# fuzz.net
KiCad netlist of a schematic drawn in Altium Designer
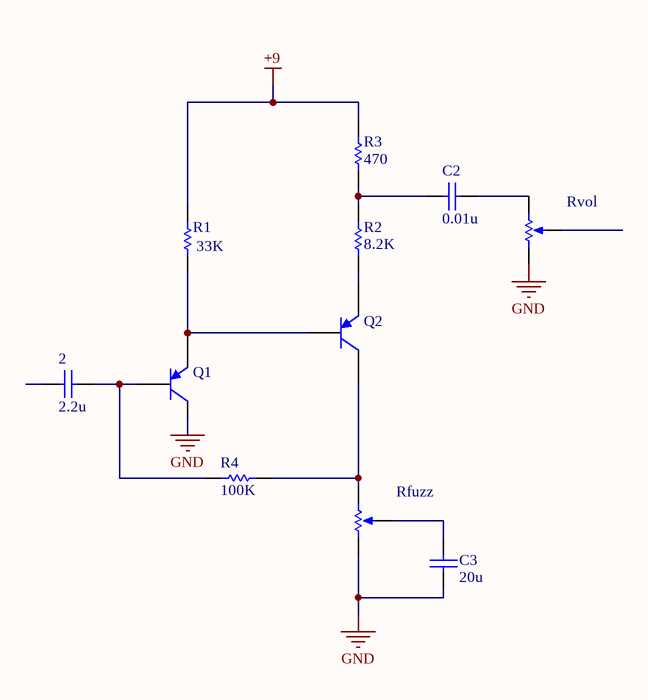
[diagram p0: fuzz.SchDoc]

(export (version "E")
  (design (tool "Eeschema 10.0.6"))
  (components
    (comp (ref "2")
      (value "2.2u")
      (description "Capacitor")
      (libsource (lib "Simulation Generic Components") (part "Capacitor"))
    )
    (comp (ref "C2")
      (value "0.01u")
      (description "Capacitor")
      (libsource (lib "Simulation Generic Components") (part "Capacitor"))
    )
    (comp (ref "C3")
      (value "20u")
      (description "Capacitor")
      (libsource (lib "Simulation Generic Components") (part "Capacitor"))
    )
    (comp (ref "Q1")
      (value "Bipolar PNP 3 Pins Transistor Gummel-Poon Model")
      (libsource (lib "Simulation Generic Components") (part "BJT PNP GP"))
    )
    (comp (ref "Q2")
      (value "Bipolar PNP 3 Pins Transistor Gummel-Poon Model")
      (libsource (lib "Simulation Generic Components") (part "BJT PNP GP"))
    )
    (comp (ref "R1")
      (value "33K")
      (description "Resistor")
      (libsource (lib "Simulation Generic Components") (part "Resistor"))
    )
    (comp (ref "R2")
      (value "8.2K")
      (description "Resistor")
      (libsource (lib "Simulation Generic Components") (part "Resistor"))
    )
    (comp (ref "R3")
      (value "470")
      (description "Resistor")
      (libsource (lib "Simulation Generic Components") (part "Resistor"))
    )
    (comp (ref "R4")
      (value "100K")
      (description "Resistor")
      (libsource (lib "Simulation Generic Components") (part "Resistor"))
    )
    (comp (ref "Rfuzz")
      (value "Potentiometer")
      (libsource (lib "Simulation Generic Components") (part "Potentiometer"))
    )
    (comp (ref "Rvol")
      (value "Potentiometer")
      (libsource (lib "Simulation Generic Components") (part "Potentiometer"))
    )
  )
  (nets
    (net (code "1") (name "+9") (class "Default")
      (node (ref "R1") (pin "1") (pinfunction "1_1") (pintype "passive"))
      (node (ref "R3") (pin "2") (pinfunction "2_2") (pintype "passive"))
    )
    (net (code "2") (name "GND") (class "Default")
      (node (ref "C3") (pin "1") (pinfunction "1_1") (pintype "passive"))
      (node (ref "Q1") (pin "1") (pinfunction "C_1") (pintype "passive"))
      (node (ref "Rfuzz") (pin "1") (pinfunction "TOP_1") (pintype "passive"))
      (node (ref "Rvol") (pin "1") (pinfunction "TOP_1") (pintype "passive"))
    )
    (net (code "3") (name "Net-(C2-Pad1)") (class "Default")
      (node (ref "C2") (pin "1") (pinfunction "1_1") (pintype "passive"))
      (node (ref "R2") (pin "2") (pinfunction "2_2") (pintype "passive"))
      (node (ref "R3") (pin "1") (pinfunction "1_1") (pintype "passive"))
    )
    (net (code "4") (name "Net-(Q1-B)") (class "Default")
      (node (ref "2") (pin "2") (pinfunction "2_2") (pintype "passive"))
      (node (ref "Q1") (pin "2") (pinfunction "B_2") (pintype "passive"))
      (node (ref "R4") (pin "2") (pinfunction "2_2") (pintype "passive"))
    )
    (net (code "5") (name "Net-(Q1-E)") (class "Default")
      (node (ref "Q1") (pin "3") (pinfunction "E_3") (pintype "passive"))
      (node (ref "Q2") (pin "2") (pinfunction "B_2") (pintype "passive"))
      (node (ref "R1") (pin "2") (pinfunction "2_2") (pintype "passive"))
    )
    (net (code "6") (name "Net-(Q2-C)") (class "Default")
      (node (ref "Q2") (pin "1") (pinfunction "C_1") (pintype "passive"))
      (node (ref "R4") (pin "1") (pinfunction "1_1") (pintype "passive"))
      (node (ref "Rfuzz") (pin "2") (pinfunction "BOT_2") (pintype "passive"))
    )
    (net (code "7") (name "Net-(Q2-E)") (class "Default")
      (node (ref "Q2") (pin "3") (pinfunction "E_3") (pintype "passive"))
      (node (ref "R2") (pin "1") (pinfunction "1_1") (pintype "passive"))
    )
    (net (code "8") (name "Net-(Rfuzz-TAP)") (class "Default")
      (node (ref "C3") (pin "2") (pinfunction "2_2") (pintype "passive"))
      (node (ref "Rfuzz") (pin "3") (pinfunction "TAP_3") (pintype "passive"))
    )
    (net (code "9") (name "Net-(Rvol-BOT)") (class "Default")
      (node (ref "C2") (pin "2") (pinfunction "2_2") (pintype "passive"))
      (node (ref "Rvol") (pin "2") (pinfunction "BOT_2") (pintype "passive"))
    )
    (net (code "10") (name "unconnected-(2-Pad1)") (class "Default")
      (node (ref "2") (pin "1") (pinfunction "1_1") (pintype "passive"))
    )
    (net (code "11") (name "unconnected-(Rvol-TAP-Pad3)") (class "Default")
      (node (ref "Rvol") (pin "3") (pinfunction "TAP_3") (pintype "passive"))
    )
  )
)
